# Snippet_HCNR201_Linearity_Analog_Optocou.net
KiCad netlist of a schematic drawn in Altium Designer
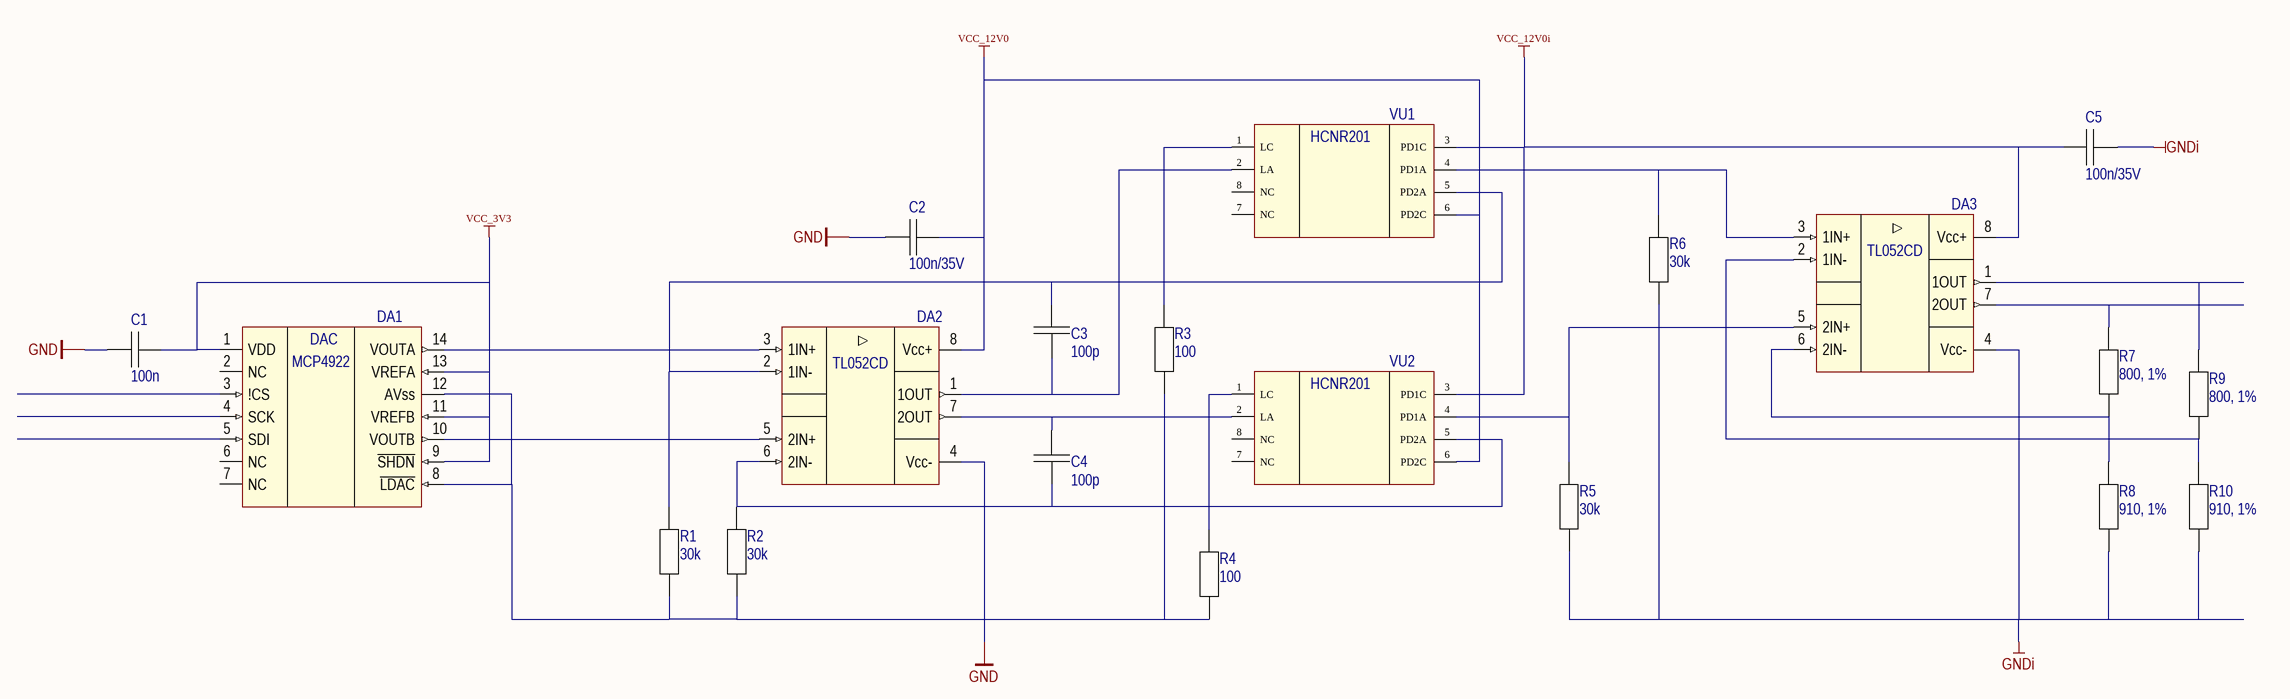
[diagram p0: Snippet_HCNR201_Linearity Analog Optocouplers.SchDoc]

(export (version "E")
  (design (tool "Eeschema 10.0.6"))
  (components
    (comp (ref "C1")
      (value "100n")
      (footprint "Capacitor_0805")
      (libsource (lib "Библиотека элементов") (part "Capacitor_0805"))
    )
    (comp (ref "C2")
      (value "100n/35V")
      (footprint "Capacitor_0805")
      (libsource (lib "Библиотека элементов") (part "Capacitor"))
    )
    (comp (ref "C3")
      (value "100p")
      (footprint "Capacitor_0805")
      (libsource (lib "Библиотека элементов") (part "Capacitor_0805"))
    )
    (comp (ref "C4")
      (value "100p")
      (footprint "Capacitor_0805")
      (libsource (lib "Библиотека элементов") (part "Capacitor_0805"))
    )
    (comp (ref "C5")
      (value "100n/35V")
      (footprint "Capacitor_0805")
      (libsource (lib "Библиотека элементов") (part "Capacitor"))
    )
    (comp (ref "DA1")
      (value "MCP4922")
      (footprint "MCP4922_SOIC14")
      (description "MCP4922-E/SL")
      (libsource (lib "Библиотека элементов") (part "MCP4922"))
    )
    (comp (ref "DA2")
      (value "TL052CD")
      (footprint "AD823_SOIC8")
      (libsource (lib "Библиотека элементов") (part "TL052CD"))
    )
    (comp (ref "DA3")
      (value "TL052CD")
      (footprint "AD823_SOIC8")
      (libsource (lib "Библиотека элементов") (part "TL052CD"))
    )
    (comp (ref "R1")
      (value "30k")
      (footprint "RESISTOR_SMD0805")
      (libsource (lib "Библиотека элементов") (part "Resistor_0805"))
    )
    (comp (ref "R2")
      (value "30k")
      (footprint "RESISTOR_SMD0805")
      (libsource (lib "Библиотека элементов") (part "Resistor_0805"))
    )
    (comp (ref "R3")
      (value "100")
      (footprint "RESISTOR_SMD0805")
      (libsource (lib "Библиотека элементов") (part "Resistor_0805"))
    )
    (comp (ref "R4")
      (value "100")
      (footprint "RESISTOR_SMD0805")
      (libsource (lib "Библиотека элементов") (part "Resistor_0805"))
    )
    (comp (ref "R5")
      (value "30k")
      (footprint "RESISTOR_SMD0805")
      (libsource (lib "Библиотека элементов") (part "Resistor_0805"))
    )
    (comp (ref "R6")
      (value "30k")
      (footprint "RESISTOR_SMD0805")
      (libsource (lib "Библиотека элементов") (part "Resistor_0805"))
    )
    (comp (ref "R7")
      (value "800, 1%")
      (footprint "RESISTOR_SMD0805")
      (libsource (lib "Библиотека элементов") (part "Resistor_0805"))
    )
    (comp (ref "R8")
      (value "910, 1%")
      (footprint "RESISTOR_SMD0805")
      (libsource (lib "Библиотека элементов") (part "Resistor_0805"))
    )
    (comp (ref "R9")
      (value "800, 1%")
      (footprint "RESISTOR_SMD0805")
      (libsource (lib "Библиотека элементов") (part "Resistor_0805"))
    )
    (comp (ref "R10")
      (value "910, 1%")
      (footprint "RESISTOR_SMD0805")
      (libsource (lib "Библиотека элементов") (part "Resistor_0805"))
    )
    (comp (ref "VU1")
      (value "HCNR201")
      (footprint "DIP-8 Widebody")
      (libsource (lib "Библиотека элементов") (part "HCNR201"))
    )
    (comp (ref "VU2")
      (value "HCNR201")
      (footprint "DIP-8 Widebody")
      (libsource (lib "Библиотека элементов") (part "HCNR201"))
    )
  )
  (nets
    (net (code "1") (name "GND") (class "Default")
      (node (ref "C1") (pin "1") (pinfunction "1_1") (pintype "passive"))
      (node (ref "C2") (pin "1") (pinfunction "1_1") (pintype "passive"))
      (node (ref "DA1") (pin "12") (pinfunction "AVss_12") (pintype "power_in"))
      (node (ref "DA1") (pin "8") (pinfunction "~{LDAC}_8") (pintype "input"))
      (node (ref "DA2") (pin "4") (pinfunction "Vcc-_4") (pintype "power_in"))
      (node (ref "R1") (pin "2") (pinfunction "2_2") (pintype "passive"))
      (node (ref "R2") (pin "2") (pinfunction "2_2") (pintype "passive"))
      (node (ref "R3") (pin "1") (pinfunction "1_1") (pintype "passive"))
      (node (ref "R4") (pin "1") (pinfunction "1_1") (pintype "passive"))
    )
    (net (code "2") (name "GNDi") (class "Default")
      (node (ref "C5") (pin "1") (pinfunction "1_1") (pintype "passive"))
      (node (ref "DA3") (pin "4") (pinfunction "Vcc-_4") (pintype "power_in"))
      (node (ref "R10") (pin "2") (pinfunction "2_2") (pintype "passive"))
      (node (ref "R5") (pin "1") (pinfunction "1_1") (pintype "passive"))
      (node (ref "R6") (pin "1") (pinfunction "1_1") (pintype "passive"))
      (node (ref "R8") (pin "2") (pinfunction "2_2") (pintype "passive"))
    )
    (net (code "3") (name "Net-(DA1-VOUTA)") (class "Default")
      (node (ref "DA1") (pin "14") (pinfunction "VOUTA_14") (pintype "output"))
      (node (ref "DA2") (pin "3") (pinfunction "1IN+_3") (pintype "input"))
    )
    (net (code "4") (name "Net-(DA1-VOUTB)") (class "Default")
      (node (ref "DA1") (pin "10") (pinfunction "VOUTB_10") (pintype "output"))
      (node (ref "DA2") (pin "5") (pinfunction "2IN+_5") (pintype "input"))
    )
    (net (code "5") (name "Net-(DA2-1IN-)") (class "Default")
      (node (ref "C3") (pin "2") (pinfunction "2_2") (pintype "passive"))
      (node (ref "DA2") (pin "2") (pinfunction "1IN-_2") (pintype "input"))
      (node (ref "R1") (pin "1") (pinfunction "1_1") (pintype "passive"))
      (node (ref "VU1") (pin "5") (pinfunction "PD2A_5") (pintype "passive"))
    )
    (net (code "6") (name "Net-(DA2-1OUT)") (class "Default")
      (node (ref "C3") (pin "1") (pinfunction "1_1") (pintype "passive"))
      (node (ref "DA2") (pin "1") (pinfunction "1OUT_1") (pintype "output"))
      (node (ref "VU1") (pin "2") (pinfunction "LA_2") (pintype "passive"))
    )
    (net (code "7") (name "Net-(DA2-2IN-)") (class "Default")
      (node (ref "C4") (pin "2") (pinfunction "2_2") (pintype "passive"))
      (node (ref "DA2") (pin "6") (pinfunction "2IN-_6") (pintype "input"))
      (node (ref "R2") (pin "1") (pinfunction "1_1") (pintype "passive"))
      (node (ref "VU2") (pin "5") (pinfunction "PD2A_5") (pintype "passive"))
    )
    (net (code "8") (name "Net-(DA2-2OUT)") (class "Default")
      (node (ref "C4") (pin "1") (pinfunction "1_1") (pintype "passive"))
      (node (ref "DA2") (pin "7") (pinfunction "2OUT_7") (pintype "output"))
      (node (ref "VU2") (pin "2") (pinfunction "LA_2") (pintype "passive"))
    )
    (net (code "9") (name "Net-(DA3-1IN+)") (class "Default")
      (node (ref "DA3") (pin "3") (pinfunction "1IN+_3") (pintype "input"))
      (node (ref "R6") (pin "2") (pinfunction "2_2") (pintype "passive"))
      (node (ref "VU1") (pin "4") (pinfunction "PD1A_4") (pintype "passive"))
    )
    (net (code "10") (name "Net-(DA3-1IN-)") (class "Default")
      (node (ref "DA3") (pin "2") (pinfunction "1IN-_2") (pintype "input"))
      (node (ref "R10") (pin "1") (pinfunction "1_1") (pintype "passive"))
      (node (ref "R9") (pin "1") (pinfunction "1_1") (pintype "passive"))
    )
    (net (code "11") (name "Net-(DA3-1OUT)") (class "Default")
      (node (ref "DA3") (pin "1") (pinfunction "1OUT_1") (pintype "output"))
      (node (ref "R9") (pin "2") (pinfunction "2_2") (pintype "passive"))
    )
    (net (code "12") (name "Net-(DA3-2IN+)") (class "Default")
      (node (ref "DA3") (pin "5") (pinfunction "2IN+_5") (pintype "input"))
      (node (ref "R5") (pin "2") (pinfunction "2_2") (pintype "passive"))
      (node (ref "VU2") (pin "4") (pinfunction "PD1A_4") (pintype "passive"))
    )
    (net (code "13") (name "Net-(DA3-2IN-)") (class "Default")
      (node (ref "DA3") (pin "6") (pinfunction "2IN-_6") (pintype "input"))
      (node (ref "R7") (pin "2") (pinfunction "2_2") (pintype "passive"))
      (node (ref "R8") (pin "1") (pinfunction "1_1") (pintype "passive"))
    )
    (net (code "14") (name "Net-(DA3-2OUT)") (class "Default")
      (node (ref "DA3") (pin "7") (pinfunction "2OUT_7") (pintype "output"))
      (node (ref "R7") (pin "1") (pinfunction "1_1") (pintype "passive"))
    )
    (net (code "15") (name "Net-(VU1-LC)") (class "Default")
      (node (ref "R3") (pin "2") (pinfunction "2_2") (pintype "passive"))
      (node (ref "VU1") (pin "1") (pinfunction "LC_1") (pintype "passive"))
    )
    (net (code "16") (name "Net-(VU2-LC)") (class "Default")
      (node (ref "R4") (pin "2") (pinfunction "2_2") (pintype "passive"))
      (node (ref "VU2") (pin "1") (pinfunction "LC_1") (pintype "passive"))
    )
    (net (code "17") (name "VCC_3V3") (class "Default")
      (node (ref "C1") (pin "2") (pinfunction "2_2") (pintype "passive"))
      (node (ref "DA1") (pin "1") (pinfunction "VDD_1") (pintype "power_in"))
      (node (ref "DA1") (pin "11") (pinfunction "VREFB_11") (pintype "input"))
      (node (ref "DA1") (pin "13") (pinfunction "VREFA_13") (pintype "input"))
      (node (ref "DA1") (pin "9") (pinfunction "~{SHDN}_9") (pintype "input"))
    )
    (net (code "18") (name "VCC_12V0") (class "Default")
      (node (ref "C2") (pin "2") (pinfunction "2_2") (pintype "passive"))
      (node (ref "DA2") (pin "8") (pinfunction "Vcc+_8") (pintype "power_in"))
      (node (ref "VU1") (pin "6") (pinfunction "PD2C_6") (pintype "passive"))
      (node (ref "VU2") (pin "6") (pinfunction "PD2C_6") (pintype "passive"))
    )
    (net (code "19") (name "VCC_12V0i") (class "Default")
      (node (ref "C5") (pin "2") (pinfunction "2_2") (pintype "passive"))
      (node (ref "DA3") (pin "8") (pinfunction "Vcc+_8") (pintype "power_in"))
      (node (ref "VU1") (pin "3") (pinfunction "PD1C_3") (pintype "passive"))
      (node (ref "VU2") (pin "3") (pinfunction "PD1C_3") (pintype "passive"))
    )
    (net (code "20") (name "unconnected-(DA1-!CS-Pad3)") (class "Default")
      (node (ref "DA1") (pin "3") (pinfunction "!CS_3") (pintype "input"))
    )
    (net (code "21") (name "unconnected-(DA1-NC-Pad2)") (class "Default")
      (node (ref "DA1") (pin "2") (pinfunction "NC_2") (pintype "passive"))
    )
    (net (code "22") (name "unconnected-(DA1-NC-Pad6)") (class "Default")
      (node (ref "DA1") (pin "6") (pinfunction "NC_6") (pintype "passive"))
    )
    (net (code "23") (name "unconnected-(DA1-NC-Pad7)") (class "Default")
      (node (ref "DA1") (pin "7") (pinfunction "NC_7") (pintype "passive"))
    )
    (net (code "24") (name "unconnected-(DA1-SCK-Pad4)") (class "Default")
      (node (ref "DA1") (pin "4") (pinfunction "SCK_4") (pintype "input"))
    )
    (net (code "25") (name "unconnected-(DA1-SDI-Pad5)") (class "Default")
      (node (ref "DA1") (pin "5") (pinfunction "SDI_5") (pintype "input"))
    )
    (net (code "26") (name "unconnected-(VU1-NC-Pad7)") (class "Default")
      (node (ref "VU1") (pin "7") (pinfunction "NC_7") (pintype "passive"))
    )
    (net (code "27") (name "unconnected-(VU1-NC-Pad8)") (class "Default")
      (node (ref "VU1") (pin "8") (pinfunction "NC_8") (pintype "passive"))
    )
    (net (code "28") (name "unconnected-(VU2-NC-Pad7)") (class "Default")
      (node (ref "VU2") (pin "7") (pinfunction "NC_7") (pintype "passive"))
    )
    (net (code "29") (name "unconnected-(VU2-NC-Pad8)") (class "Default")
      (node (ref "VU2") (pin "8") (pinfunction "NC_8") (pintype "passive"))
    )
  )
)
